# V1_sch.net
KiCad netlist of a schematic drawn in Altium Designer
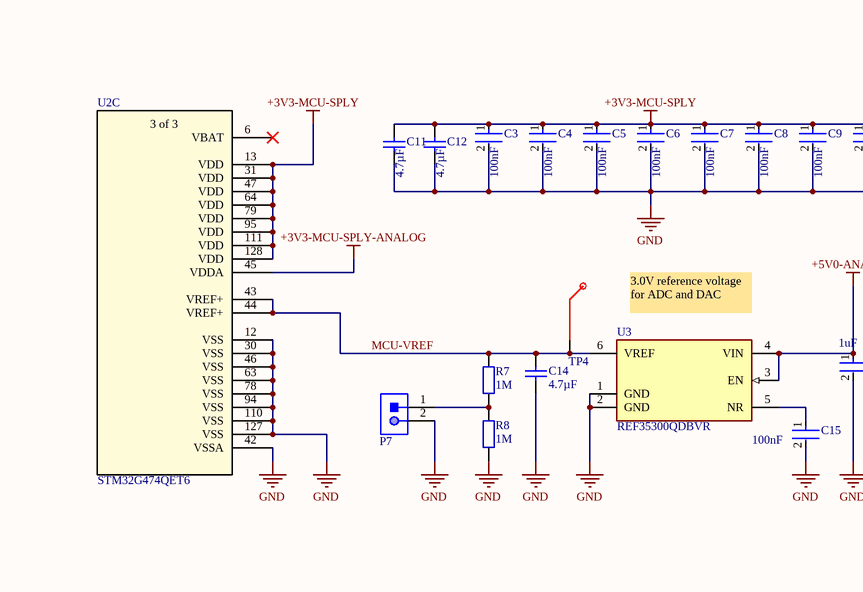
[diagram p0: V1_sch.SchDoc, top left]
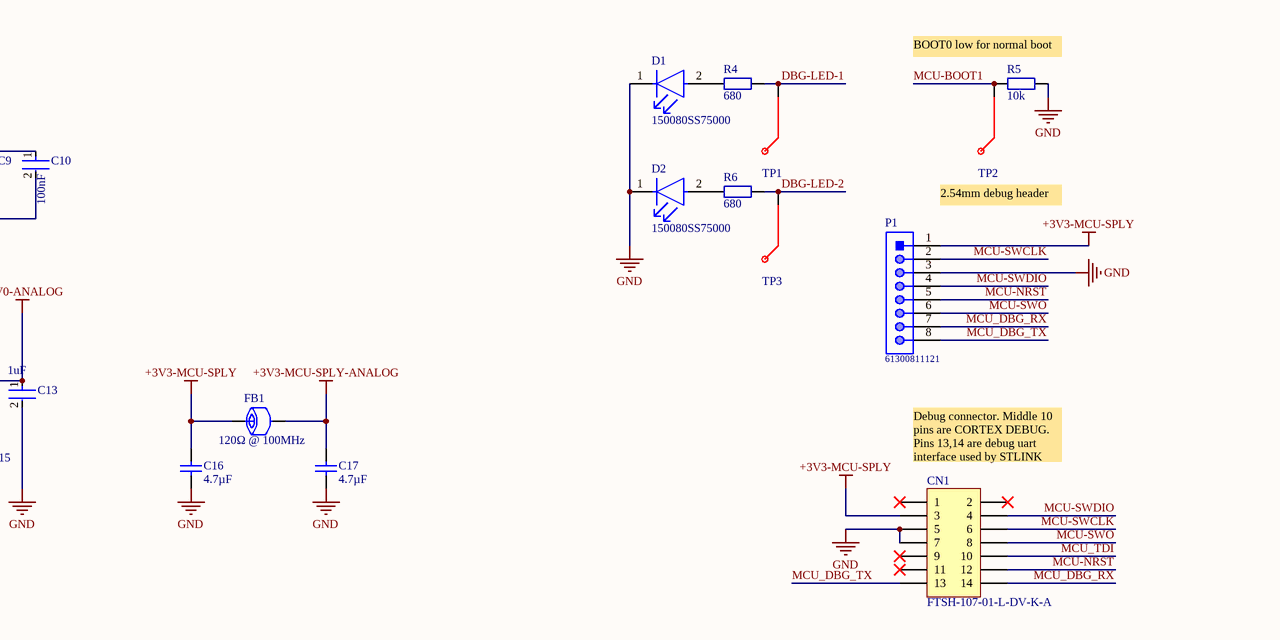
[diagram p1: V1_sch.SchDoc, top right]
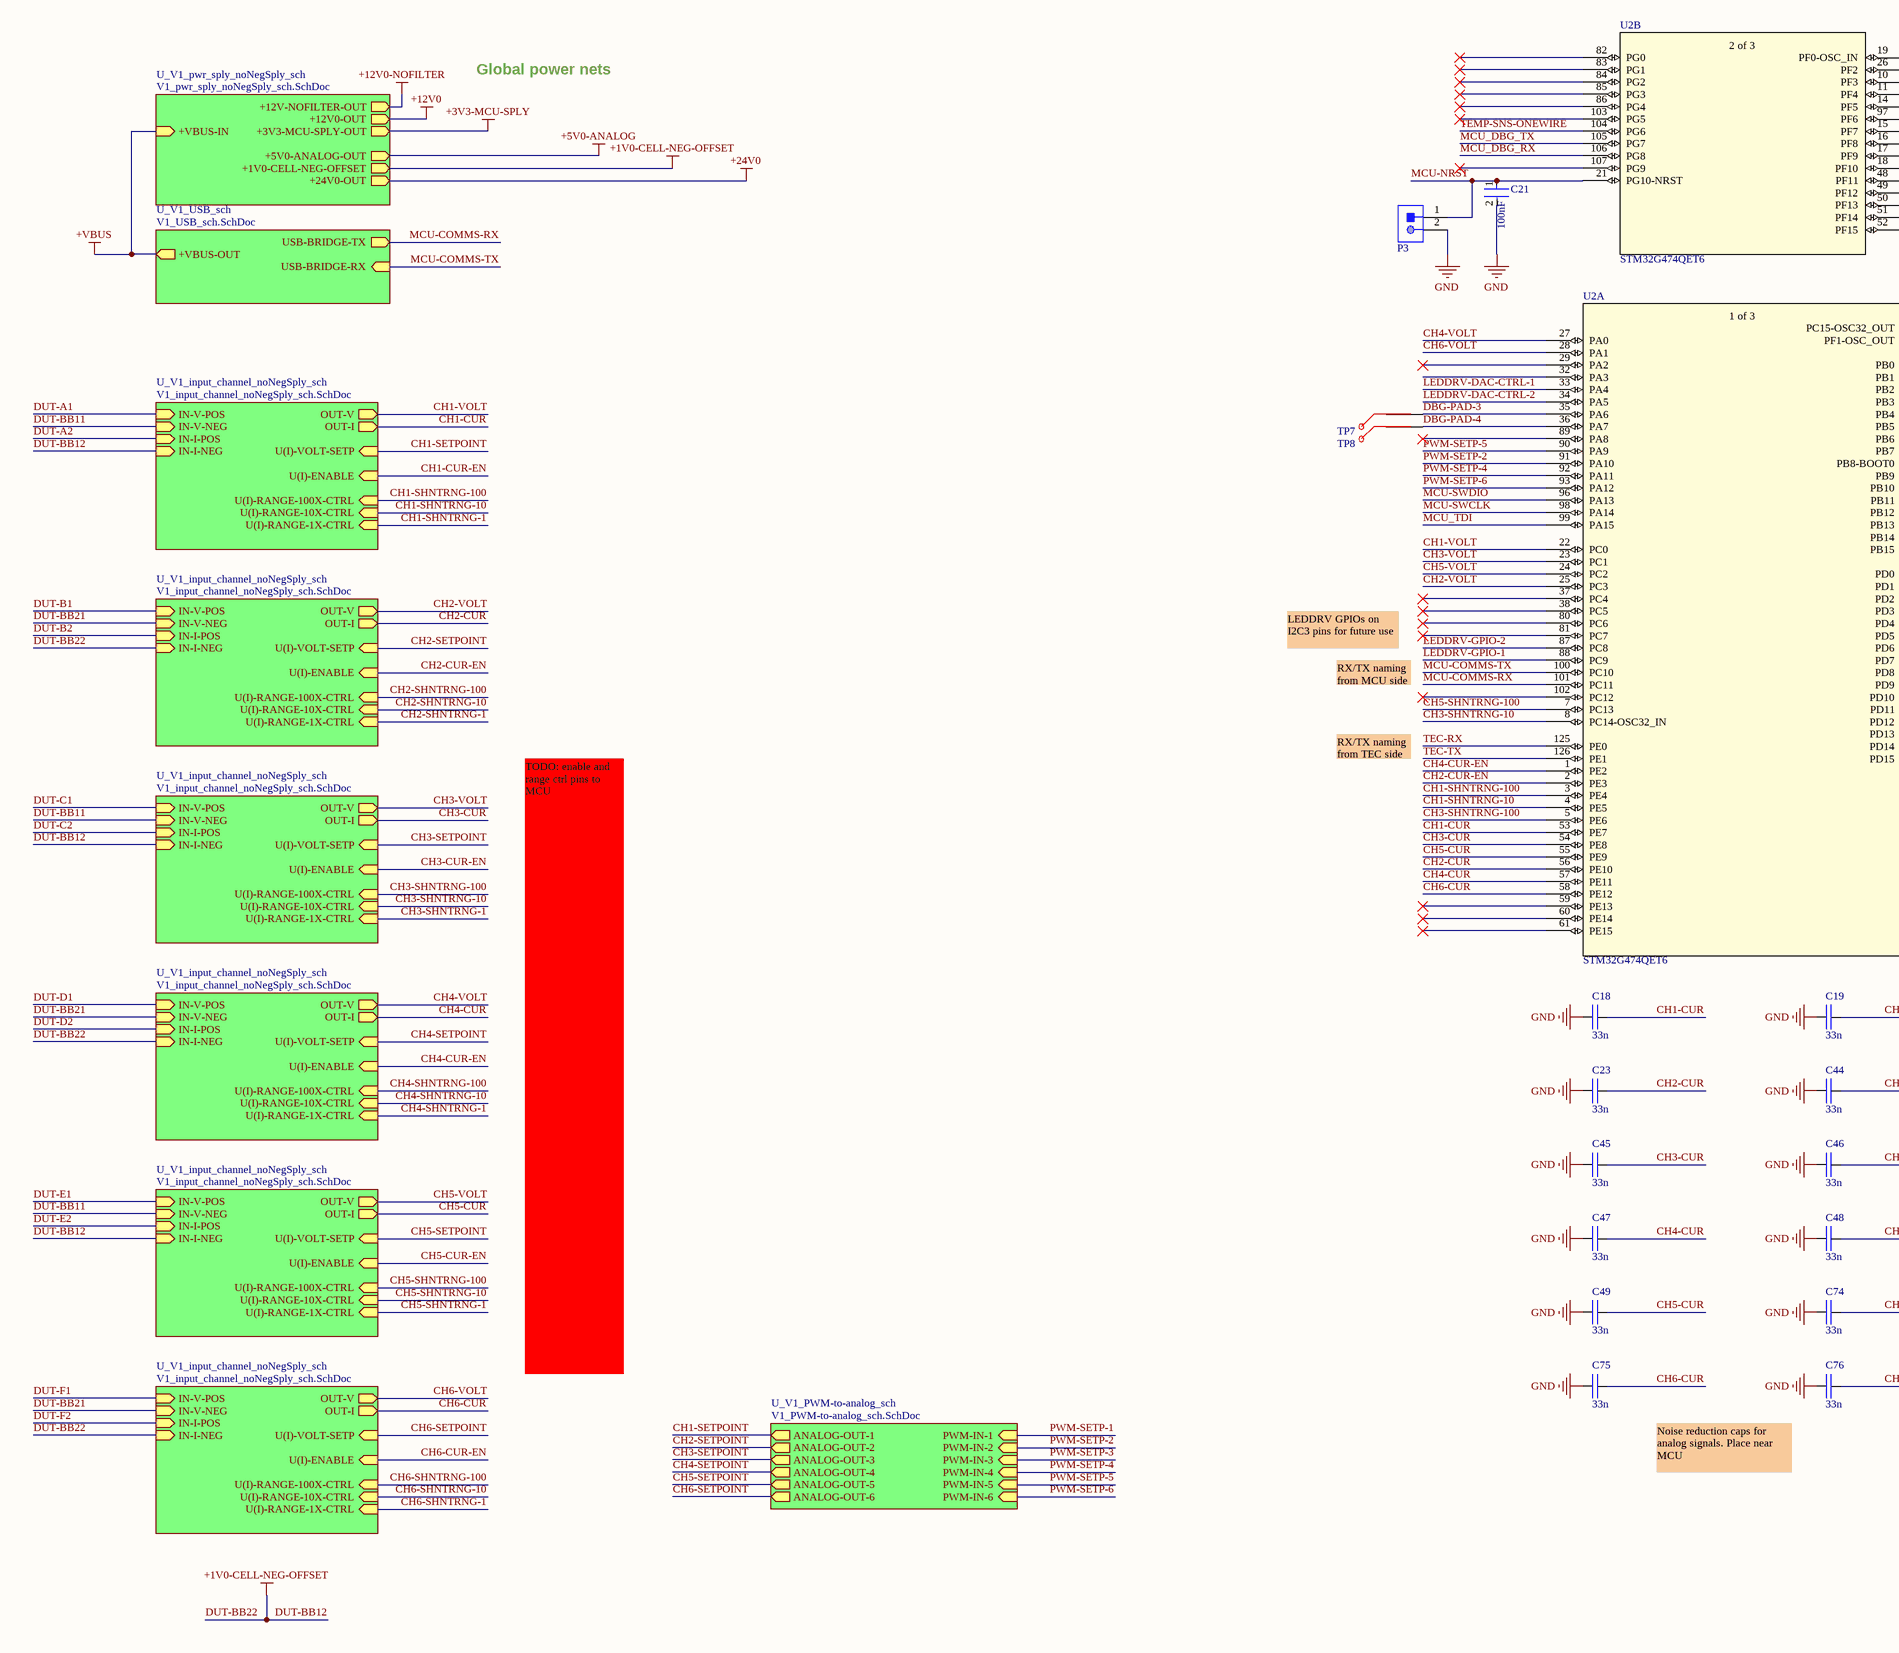
[diagram p2: V1_sch.SchDoc, bottom left]
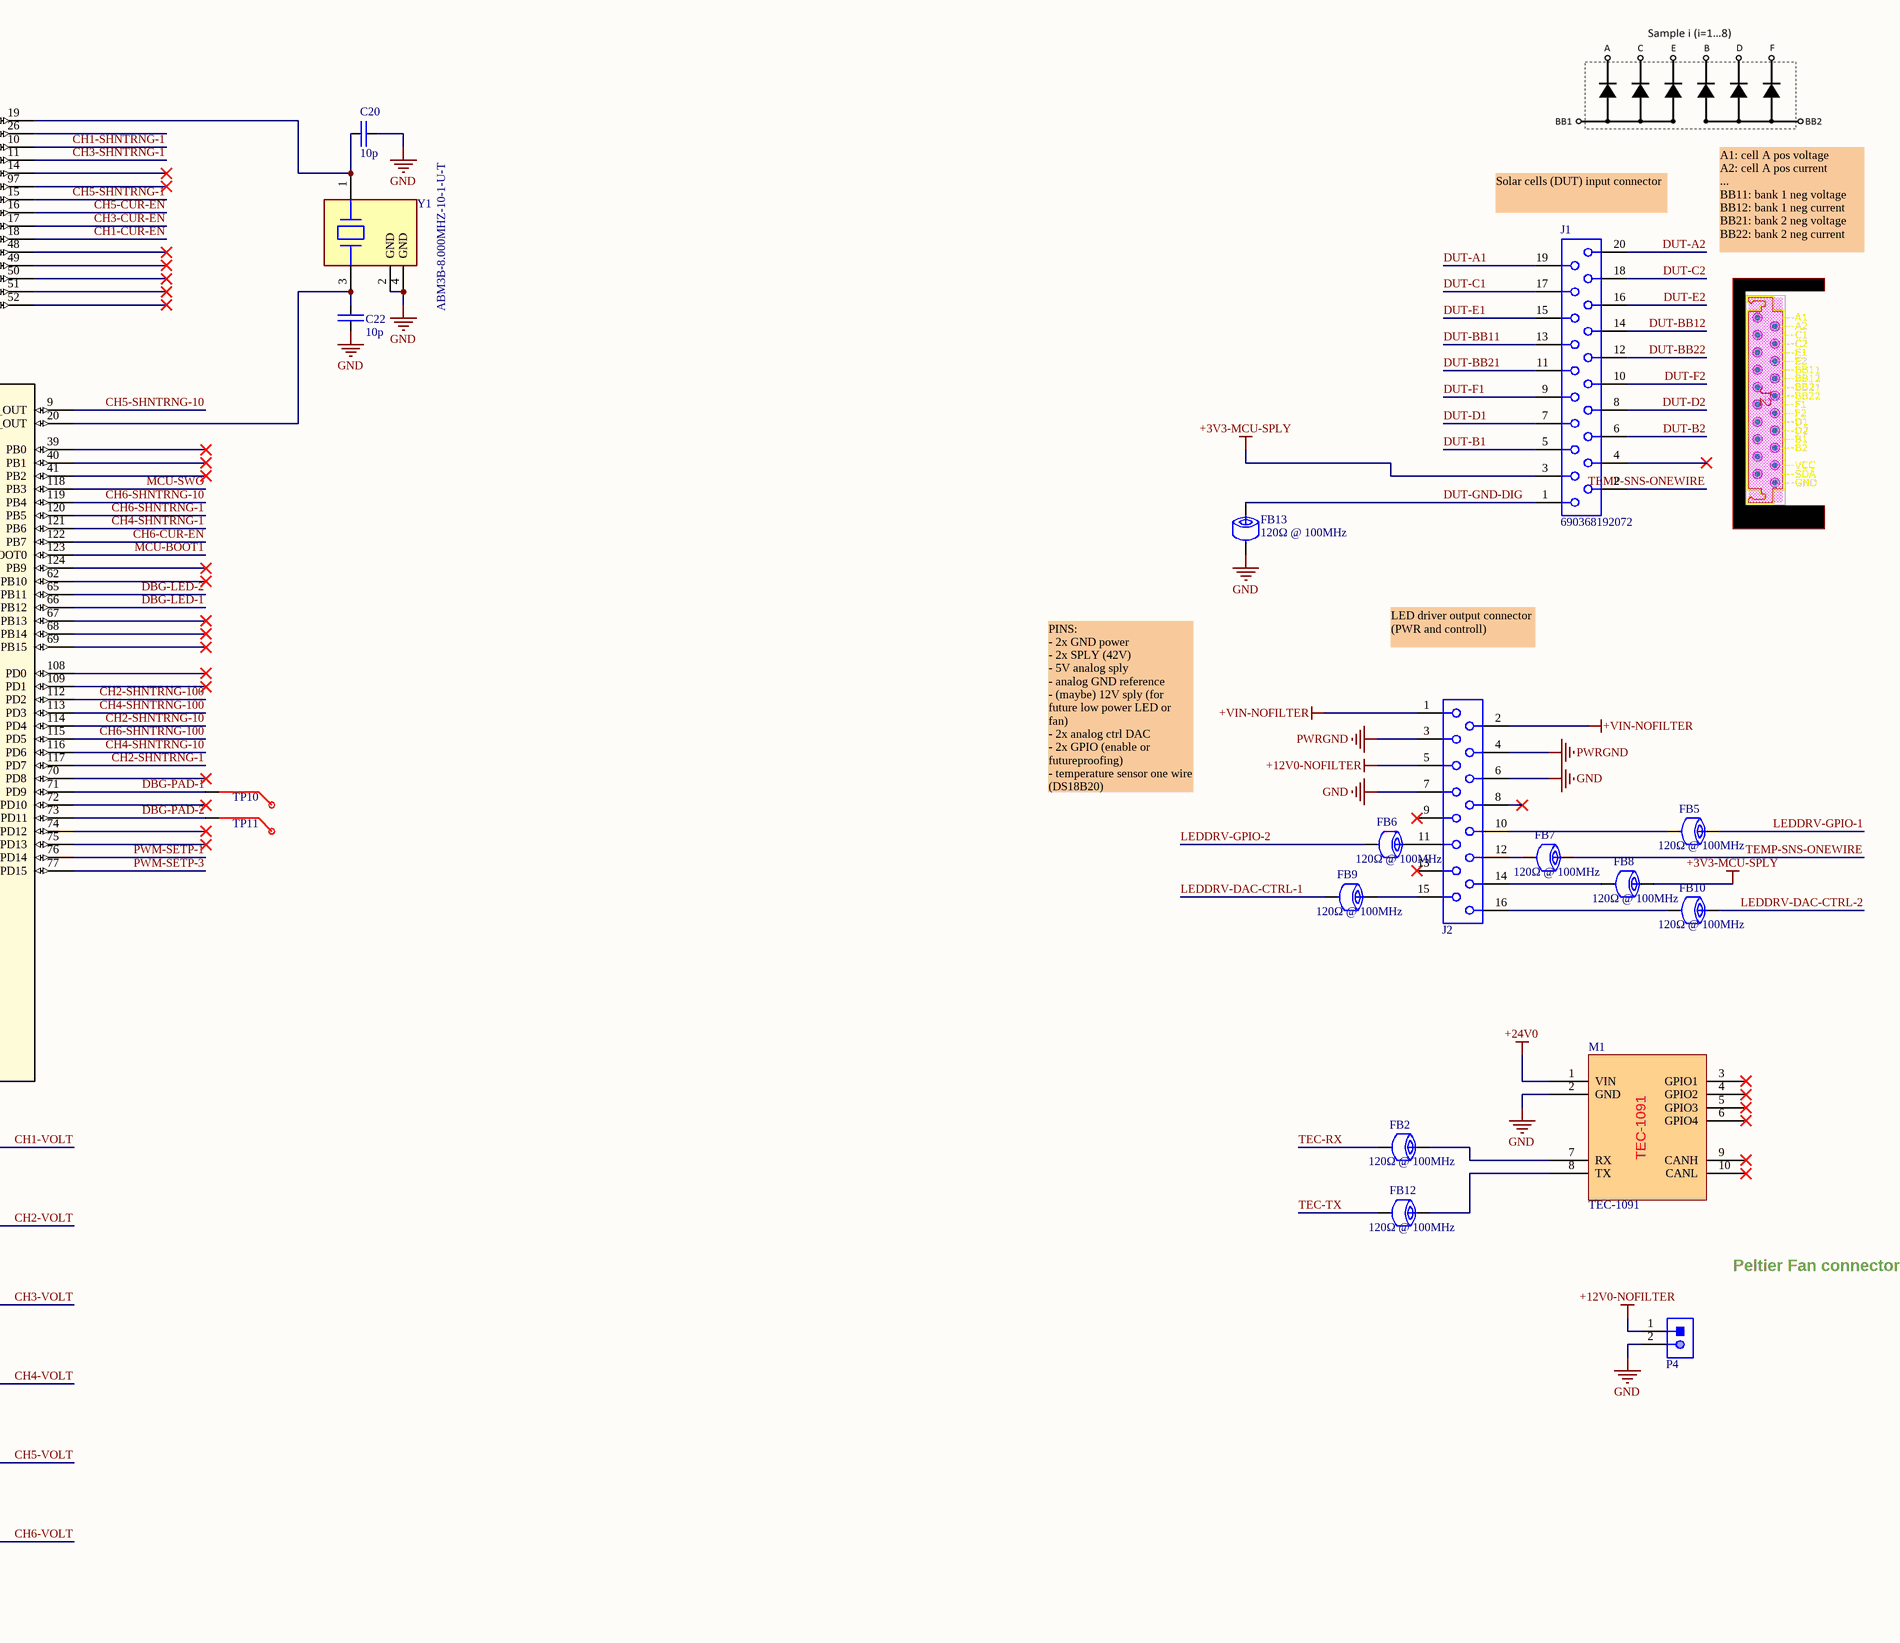
[diagram p3: V1_sch.SchDoc, bottom right]

(export (version "E")
  (design (tool "Eeschema 10.0.6"))
  (components
    (comp (ref "C3")
      (value "885012206095")
      (footprint "FP-885012206095-IPC_B")
      (description "CAP CER 0.1UF 50V X7R 0603")
      (fields (field (name "TOLERANCE") "10%") (field (name "CAPACITANCE") "100nF"))
      (libsource (lib "Altium Content Vault") (part "11868f565c42a9108669ba33697ecf6"))
    )
    (comp (ref "C4")
      (value "885012206095")
      (footprint "FP-885012206095-IPC_B")
      (description "CAP CER 0.1UF 50V X7R 0603")
      (fields (field (name "TOLERANCE") "10%") (field (name "CAPACITANCE") "100nF"))
      (libsource (lib "Altium Content Vault") (part "11868f565c42a9108669ba33697ecf6"))
    )
    (comp (ref "C5")
      (value "885012206095")
      (footprint "FP-885012206095-IPC_B")
      (description "CAP CER 0.1UF 50V X7R 0603")
      (fields (field (name "TOLERANCE") "10%") (field (name "CAPACITANCE") "100nF"))
      (libsource (lib "Altium Content Vault") (part "11868f565c42a9108669ba33697ecf6"))
    )
    (comp (ref "C6")
      (value "885012206095")
      (footprint "FP-885012206095-IPC_B")
      (description "CAP CER 0.1UF 50V X7R 0603")
      (fields (field (name "TOLERANCE") "10%") (field (name "CAPACITANCE") "100nF"))
      (libsource (lib "Altium Content Vault") (part "11868f565c42a9108669ba33697ecf6"))
    )
    (comp (ref "C7")
      (value "885012206095")
      (footprint "FP-885012206095-IPC_B")
      (description "CAP CER 0.1UF 50V X7R 0603")
      (fields (field (name "TOLERANCE") "10%") (field (name "CAPACITANCE") "100nF"))
      (libsource (lib "Altium Content Vault") (part "11868f565c42a9108669ba33697ecf6"))
    )
    (comp (ref "C8")
      (value "885012206095")
      (footprint "FP-885012206095-IPC_B")
      (description "CAP CER 0.1UF 50V X7R 0603")
      (fields (field (name "TOLERANCE") "10%") (field (name "CAPACITANCE") "100nF"))
      (libsource (lib "Altium Content Vault") (part "11868f565c42a9108669ba33697ecf6"))
    )
    (comp (ref "C9")
      (value "885012206095")
      (footprint "FP-885012206095-IPC_B")
      (description "CAP CER 0.1UF 50V X7R 0603")
      (fields (field (name "TOLERANCE") "10%") (field (name "CAPACITANCE") "100nF"))
      (libsource (lib "Altium Content Vault") (part "11868f565c42a9108669ba33697ecf6"))
    )
    (comp (ref "C10")
      (value "885012206095")
      (footprint "FP-885012206095-IPC_B")
      (description "CAP CER 0.1UF 50V X7R 0603")
      (fields (field (name "TOLERANCE") "10%") (field (name "CAPACITANCE") "100nF"))
      (libsource (lib "Altium Content Vault") (part "11868f565c42a9108669ba33697ecf6"))
    )
    (comp (ref "C11")
      (value "885012107018")
      (footprint "WCAP-CSGP_0805_L2W1.25H1.25")
      (description "WCAP-CSGP Multilayer Ceramic Chip Capacitor, General Purpose, size 0805, X5R, 4.7µF, 25VDC")
      (fields (field (name "MANUFACTURER") "Wurth Elektronik") (field (name "CAPACITANCE") "4.7µF"))
      (libsource (lib "Altium_WCAP-CSGP (rev22f)") (part "885012107018"))
    )
    (comp (ref "C12")
      (value "885012107018")
      (footprint "WCAP-CSGP_0805_L2W1.25H1.25")
      (description "WCAP-CSGP Multilayer Ceramic Chip Capacitor, General Purpose, size 0805, X5R, 4.7µF, 25VDC")
      (fields (field (name "MANUFACTURER") "Wurth Elektronik") (field (name "CAPACITANCE") "4.7µF"))
      (libsource (lib "Altium_WCAP-CSGP (rev22f)") (part "885012107018"))
    )
    (comp (ref "C13")
      (value "885012207078")
      (footprint "FP-885012207078-IPC_B")
      (description "CAP CER 1UF 25V X7R 0805")
      (fields (field (name "CAPACITANCE") "1uF") (field (name "TOLERANCE") "10%"))
      (libsource (lib "Altium Content Vault") (part "b4654b650e69147ec39a6b967a45e02"))
    )
    (comp (ref "C14")
      (value "885012107018")
      (footprint "WCAP-CSGP_0805_L2W1.25H1.25")
      (description "WCAP-CSGP Multilayer Ceramic Chip Capacitor, General Purpose, size 0805, X5R, 4.7µF, 25VDC")
      (fields (field (name "MANUFACTURER") "Wurth Elektronik") (field (name "CAPACITANCE") "4.7µF"))
      (libsource (lib "Altium_WCAP-CSGP (rev22f)") (part "885012107018"))
    )
    (comp (ref "C15")
      (value "885012206095")
      (footprint "FP-885012206095-IPC_B")
      (description "CAP CER 0.1UF 50V X7R 0603")
      (fields (field (name "TOLERANCE") "10%") (field (name "CAPACITANCE") "100nF"))
      (libsource (lib "Altium Content Vault") (part "11868f565c42a9108669ba33697ecf6"))
    )
    (comp (ref "C16")
      (value "885012107018")
      (footprint "WCAP-CSGP_0805_L2W1.25H1.25")
      (description "WCAP-CSGP Multilayer Ceramic Chip Capacitor, General Purpose, size 0805, X5R, 4.7µF, 25VDC")
      (fields (field (name "MANUFACTURER") "Wurth Elektronik") (field (name "CAPACITANCE") "4.7µF"))
      (libsource (lib "Altium_WCAP-CSGP (rev22f)") (part "885012107018"))
    )
    (comp (ref "C17")
      (value "885012107018")
      (footprint "WCAP-CSGP_0805_L2W1.25H1.25")
      (description "WCAP-CSGP Multilayer Ceramic Chip Capacitor, General Purpose, size 0805, X5R, 4.7µF, 25VDC")
      (fields (field (name "MANUFACTURER") "Wurth Elektronik") (field (name "CAPACITANCE") "4.7µF"))
      (libsource (lib "Altium_WCAP-CSGP (rev22f)") (part "885012107018"))
    )
    (comp (ref "C18")
      (value "33n")
      (footprint "Passives:FPR_0603_C_R0")
      (description "Capacitor - generic SMD")
      (fields (field (name "Comment") "PN_C0603_TBD"))
      (libsource (lib "Passives") (part "C"))
    )
    (comp (ref "C19")
      (value "33n")
      (footprint "Passives:FPR_0603_C_R0")
      (description "Capacitor - generic SMD")
      (fields (field (name "Comment") "PN_C0603_TBD"))
      (libsource (lib "Passives") (part "C"))
    )
    (comp (ref "C20")
      (value "10p")
      (footprint "Passives:FPR_0603_C_R0")
      (description "Capacitor - generic SMD")
      (fields (field (name "Comment") "PN_C0603_10p"))
      (libsource (lib "Passives") (part "C"))
    )
    (comp (ref "C21")
      (value "885012206095")
      (footprint "FP-885012206095-IPC_B")
      (description "CAP CER 0.1UF 50V X7R 0603")
      (fields (field (name "TOLERANCE") "10%") (field (name "CAPACITANCE") "100nF"))
      (libsource (lib "Altium Content Vault") (part "11868f565c42a9108669ba33697ecf6"))
    )
    (comp (ref "C22")
      (value "10p")
      (footprint "Passives:FPR_0603_C_R0")
      (description "Capacitor - generic SMD")
      (fields (field (name "Comment") "PN_C0603_10p"))
      (libsource (lib "Passives") (part "C"))
    )
    (comp (ref "C23")
      (value "33n")
      (footprint "Passives:FPR_0603_C_R0")
      (description "Capacitor - generic SMD")
      (fields (field (name "Comment") "PN_C0603_TBD"))
      (libsource (lib "Passives") (part "C"))
    )
    (comp (ref "C44")
      (value "33n")
      (footprint "Passives:FPR_0603_C_R0")
      (description "Capacitor - generic SMD")
      (fields (field (name "Comment") "PN_C0603_TBD"))
      (libsource (lib "Passives") (part "C"))
    )
    (comp (ref "C45")
      (value "33n")
      (footprint "Passives:FPR_0603_C_R0")
      (description "Capacitor - generic SMD")
      (fields (field (name "Comment") "PN_C0603_TBD"))
      (libsource (lib "Passives") (part "C"))
    )
    (comp (ref "C46")
      (value "33n")
      (footprint "Passives:FPR_0603_C_R0")
      (description "Capacitor - generic SMD")
      (fields (field (name "Comment") "PN_C0603_TBD"))
      (libsource (lib "Passives") (part "C"))
    )
    (comp (ref "C47")
      (value "33n")
      (footprint "Passives:FPR_0603_C_R0")
      (description "Capacitor - generic SMD")
      (fields (field (name "Comment") "PN_C0603_TBD"))
      (libsource (lib "Passives") (part "C"))
    )
    (comp (ref "C48")
      (value "33n")
      (footprint "Passives:FPR_0603_C_R0")
      (description "Capacitor - generic SMD")
      (fields (field (name "Comment") "PN_C0603_TBD"))
      (libsource (lib "Passives") (part "C"))
    )
    (comp (ref "C49")
      (value "33n")
      (footprint "Passives:FPR_0603_C_R0")
      (description "Capacitor - generic SMD")
      (fields (field (name "Comment") "PN_C0603_TBD"))
      (libsource (lib "Passives") (part "C"))
    )
    (comp (ref "C74")
      (value "33n")
      (footprint "Passives:FPR_0603_C_R0")
      (description "Capacitor - generic SMD")
      (fields (field (name "Comment") "PN_C0603_TBD"))
      (libsource (lib "Passives") (part "C"))
    )
    (comp (ref "C75")
      (value "33n")
      (footprint "Passives:FPR_0603_C_R0")
      (description "Capacitor - generic SMD")
      (fields (field (name "Comment") "PN_C0603_TBD"))
      (libsource (lib "Passives") (part "C"))
    )
    (comp (ref "C76")
      (value "33n")
      (footprint "Passives:FPR_0603_C_R0")
      (description "Capacitor - generic SMD")
      (fields (field (name "Comment") "PN_C0603_TBD"))
      (libsource (lib "Passives") (part "C"))
    )
    (comp (ref "CN1")
      (value "FTSH-107-01-L-DV-K-A")
      (footprint "CON_STDC14_Receiver_MEDIUM_WITH_MIPI10_3D")
      (libsource (lib "IMS_library") (part "FTSH-107-01-L-DV-K-A"))
    )
    (comp (ref "D1")
      (value "150080SS75000")
      (footprint "FP-150080SS75000-MFG")
      (description "LED RED CLEAR 0805 SMD")
      (libsource (lib "Altium Content Vault") (part "8706943c75ba83719d021d2fdc84c58"))
    )
    (comp (ref "D2")
      (value "150080SS75000")
      (footprint "FP-150080SS75000-MFG")
      (description "LED RED CLEAR 0805 SMD")
      (libsource (lib "Altium Content Vault") (part "8706943c75ba83719d021d2fdc84c58"))
    )
    (comp (ref "FB1")
      (value "120Ω @ 100MHz")
      (footprint "SMD_0805")
      (description "Ferrite Bead, 0805 [2012 Metric], 120 ohm, 800 mA, BLM21A Series, 0.15 ohm, ± 25%")
      (fields (field (name "MANUFACTURER") "Murata"))
      (libsource (lib "DAQ_REV_B") (part "BLM21AG121SN1D"))
    )
    (comp (ref "FB2")
      (value "120Ω @ 100MHz")
      (footprint "SMD_0805")
      (description "Ferrite Bead, 0805 [2012 Metric], 120 ohm, 800 mA, BLM21A Series, 0.15 ohm, ± 25%")
      (fields (field (name "MANUFACTURER") "Murata"))
      (libsource (lib "DAQ_REV_B") (part "BLM21AG121SN1D"))
    )
    (comp (ref "FB5")
      (value "120Ω @ 100MHz")
      (footprint "SMD_0805")
      (description "Ferrite Bead, 0805 [2012 Metric], 120 ohm, 800 mA, BLM21A Series, 0.15 ohm, ± 25%")
      (fields (field (name "MANUFACTURER") "Murata"))
      (libsource (lib "DAQ_REV_B") (part "BLM21AG121SN1D"))
    )
    (comp (ref "FB6")
      (value "120Ω @ 100MHz")
      (footprint "SMD_0805")
      (description "Ferrite Bead, 0805 [2012 Metric], 120 ohm, 800 mA, BLM21A Series, 0.15 ohm, ± 25%")
      (fields (field (name "MANUFACTURER") "Murata"))
      (libsource (lib "DAQ_REV_B") (part "BLM21AG121SN1D"))
    )
    (comp (ref "FB7")
      (value "120Ω @ 100MHz")
      (footprint "SMD_0805")
      (description "Ferrite Bead, 0805 [2012 Metric], 120 ohm, 800 mA, BLM21A Series, 0.15 ohm, ± 25%")
      (fields (field (name "MANUFACTURER") "Murata"))
      (libsource (lib "DAQ_REV_B") (part "BLM21AG121SN1D"))
    )
    (comp (ref "FB8")
      (value "120Ω @ 100MHz")
      (footprint "SMD_0805")
      (description "Ferrite Bead, 0805 [2012 Metric], 120 ohm, 800 mA, BLM21A Series, 0.15 ohm, ± 25%")
      (fields (field (name "MANUFACTURER") "Murata"))
      (libsource (lib "DAQ_REV_B") (part "BLM21AG121SN1D"))
    )
    (comp (ref "FB9")
      (value "120Ω @ 100MHz")
      (footprint "SMD_0805")
      (description "Ferrite Bead, 0805 [2012 Metric], 120 ohm, 800 mA, BLM21A Series, 0.15 ohm, ± 25%")
      (fields (field (name "MANUFACTURER") "Murata"))
      (libsource (lib "DAQ_REV_B") (part "BLM21AG121SN1D"))
    )
    (comp (ref "FB10")
      (value "120Ω @ 100MHz")
      (footprint "SMD_0805")
      (description "Ferrite Bead, 0805 [2012 Metric], 120 ohm, 800 mA, BLM21A Series, 0.15 ohm, ± 25%")
      (fields (field (name "MANUFACTURER") "Murata"))
      (libsource (lib "DAQ_REV_B") (part "BLM21AG121SN1D"))
    )
    (comp (ref "FB12")
      (value "120Ω @ 100MHz")
      (footprint "SMD_0805")
      (description "Ferrite Bead, 0805 [2012 Metric], 120 ohm, 800 mA, BLM21A Series, 0.15 ohm, ± 25%")
      (fields (field (name "MANUFACTURER") "Murata"))
      (libsource (lib "DAQ_REV_B") (part "BLM21AG121SN1D"))
    )
    (comp (ref "FB13")
      (value "120Ω @ 100MHz")
      (footprint "SMD_0805")
      (description "Ferrite Bead, 0805 [2012 Metric], 120 ohm, 800 mA, BLM21A Series, 0.15 ohm, ± 25%")
      (fields (field (name "MANUFACTURER") "Murata"))
      (libsource (lib "DAQ_REV_B") (part "BLM21AG121SN1D"))
    )
    (comp (ref "J1")
      (value "690368192072")
      (footprint "690368192072")
      (description "WR-MM Mini Module Connector, Female, THT, with Latch & Polarization, Angled, pitch 2.54mm, 20p")
      (fields (field (name "MANUFACTURER") "Wurth Elektronik"))
      (libsource (lib "Altium_WR-MM (rev22a)") (part "690368192072"))
    )
    (comp (ref "J2")
      (value "690368191672")
      (footprint "690368191672")
      (description "WR-MM Mini Module Connector, Female, THT, with Latch & Polarization, Angled, pitch 2.54mm, 16p")
      (fields (field (name "MANUFACTURER") "Wurth Elektronik"))
      (libsource (lib "Altium_WR-MM (rev22a)") (part "690368191672"))
    )
    (comp (ref "M1")
      (value "TEC-1091")
      (footprint "tec1091-pins")
      (description "Peltier control module")
      (libsource (lib "TEC1091") (part "TEC-1091"))
    )
    (comp (ref "P1")
      (value "61300811121")
      (footprint "61300811121")
      (description "THT Vertical Pin Header WR-PHD, Pitch 2.54 mm, Single Row, 8 pins")
      (fields (field (name "MANUFACTURER") "Wurth Elektronik") (field (name "PUBLISHER") "WurthElektronik"))
      (libsource (lib "Components - 22.06.23 - 11.05") (part "CMP-1502-01076-1"))
    )
    (comp (ref "P3")
      (value "61300211121")
      (footprint "61300211121")
      (description "THT Vertical Pin Header WR-PHD, Pitch 2.54 mm, Single Row, 2 pins")
      (fields (field (name "MANUFACTURER") "Wurth Elektronik") (field (name "PUBLISHER") "WurthElektronik"))
      (libsource (lib "Altium Content Vault") (part "WE-CN-1P-M-R2"))
    )
    (comp (ref "P4")
      (value "61300211121")
      (footprint "61300211121")
      (description "THT Vertical Pin Header WR-PHD, Pitch 2.54 mm, Single Row, 2 pins")
      (fields (field (name "MANUFACTURER") "Wurth Elektronik") (field (name "PUBLISHER") "WurthElektronik"))
      (libsource (lib "") (part "WE-CN-1P-M-R2_1"))
    )
    (comp (ref "P7")
      (value "61300211121")
      (footprint "61300211121")
      (description "THT Vertical Pin Header WR-PHD, Pitch 2.54 mm, Single Row, 2 pins")
      (fields (field (name "MANUFACTURER") "Wurth Elektronik") (field (name "PUBLISHER") "WurthElektronik"))
      (libsource (lib "Altium Content Vault") (part "WE-CN-1P-M-R2"))
    )
    (comp (ref "R4")
      (value "680")
      (footprint "Passives:FPR_0603_R_R0")
      (description "Resistor - generic SMD")
      (fields (field (name "Comment") "PN_R0603_680R"))
      (libsource (lib "Passives") (part "R"))
    )
    (comp (ref "R5")
      (value "10k")
      (footprint "Passives:FPR_0603_R_R0")
      (description "Resistor - generic SMD")
      (fields (field (name "Comment") "PN_R0603_10k"))
      (libsource (lib "Passives") (part "R"))
    )
    (comp (ref "R6")
      (value "680")
      (footprint "Passives:FPR_0603_R_R0")
      (description "Resistor - generic SMD")
      (fields (field (name "Comment") "PN_R0603_680R"))
      (libsource (lib "Passives") (part "R"))
    )
    (comp (ref "R7")
      (value "1M")
      (footprint "Passives:FPR_0603_R_R0")
      (description "Resistor - generic SMD")
      (fields (field (name "Comment") "PN_R0603_1M"))
      (libsource (lib "Passives") (part "R"))
    )
    (comp (ref "R8")
      (value "1M")
      (footprint "Passives:FPR_0603_R_R0")
      (description "Resistor - generic SMD")
      (fields (field (name "Comment") "PN_R0603_1M"))
      (libsource (lib "Passives") (part "R"))
    )
    (comp (ref "TP1")
      (value "Test Point")
      (footprint "Test Point 1.5mm SMD")
      (libsource (lib "planinsekLib_sch") (part "Test Point"))
    )
    (comp (ref "TP2")
      (value "Test Point")
      (footprint "Test Point 1.5mm SMD")
      (libsource (lib "planinsekLib_sch") (part "Test Point"))
    )
    (comp (ref "TP3")
      (value "Test Point")
      (footprint "Test Point 1.5mm SMD")
      (libsource (lib "planinsekLib_sch") (part "Test Point"))
    )
    (comp (ref "TP4")
      (value "Test Point")
      (footprint "Test Point 1.5mm SMD")
      (libsource (lib "planinsekLib_sch") (part "Test Point"))
    )
    (comp (ref "TP7")
      (value "Test Point")
      (footprint "Test Point 1.5mm SMD")
      (libsource (lib "planinsekLib_sch") (part "Test Point"))
    )
    (comp (ref "TP8")
      (value "Test Point")
      (footprint "Test Point 1.5mm SMD")
      (libsource (lib "planinsekLib_sch") (part "Test Point"))
    )
    (comp (ref "TP10")
      (value "Test Point")
      (footprint "Test Point 1.5mm SMD")
      (libsource (lib "planinsekLib_sch") (part "Test Point"))
    )
    (comp (ref "TP11")
      (value "Test Point")
      (footprint "Test Point 1.5mm SMD")
      (libsource (lib "planinsekLib_sch") (part "Test Point"))
    )
    (comp (ref "U2")
      (value "STM32G474QET6")
      (footprint "LPQFP-128")
      (description "No Description Available")
      (libsource (lib "") (part "STM32G474QET6_1"))
    )
    (comp (ref "U3")
      (value "REF35300QDBVR")
      (footprint "FP-DBV0006A-MFG")
      (description "650-NA QUIESCENT CURRENT, 12-PPM, 3V out")
      (libsource (lib "Altium Content Vault") (part "73067d3f248247d8aed0d86424b3493"))
    )
    (comp (ref "Y1")
      (value "ABM3B-8.000MHZ-10-1-U-T")
      (footprint "FP-ABM3B-MFG")
      (description "Crystal 8MHz ±10ppm 10pF SMD-4 5mm x 3.2mm")
      (libsource (lib "Altium Content Vault") (part "48e526d86b7f2615d98721063c72f49"))
    )
  )
  (nets
    (net (code "1") (name "+1V0-CELL-NEG-OFFSET") (class "Default")
      (node (ref "J1") (pin "12") (pinfunction "12_12") (pintype "passive"))
      (node (ref "J1") (pin "14") (pinfunction "14_14") (pintype "passive"))
    )
    (net (code "2") (name "+3V3-MCU-SPLY") (class "Default")
      (node (ref "C10") (pin "1") (pinfunction "1_1") (pintype "passive"))
      (node (ref "C11") (pin "2") (pinfunction "2_2") (pintype "passive"))
      (node (ref "C12") (pin "2") (pinfunction "2_2") (pintype "passive"))
      (node (ref "C16") (pin "2") (pinfunction "2_2") (pintype "passive"))
      (node (ref "C3") (pin "1") (pinfunction "1_1") (pintype "passive"))
      (node (ref "C4") (pin "1") (pinfunction "1_1") (pintype "passive"))
      (node (ref "C5") (pin "1") (pinfunction "1_1") (pintype "passive"))
      (node (ref "C6") (pin "1") (pinfunction "1_1") (pintype "passive"))
      (node (ref "C7") (pin "1") (pinfunction "1_1") (pintype "passive"))
      (node (ref "C8") (pin "1") (pinfunction "1_1") (pintype "passive"))
      (node (ref "C9") (pin "1") (pinfunction "1_1") (pintype "passive"))
      (node (ref "CN1") (pin "3") (pinfunction "3_3") (pintype "passive"))
      (node (ref "FB1") (pin "1") (pintype "passive"))
      (node (ref "FB8") (pin "1") (pintype "passive"))
      (node (ref "J1") (pin "3") (pinfunction "3_3") (pintype "passive"))
      (node (ref "P1") (pin "1") (pinfunction "1_1") (pintype "passive"))
      (node (ref "U2") (pin "111") (pinfunction "VDD_111") (pintype "power_in"))
      (node (ref "U2") (pin "128") (pinfunction "VDD_128") (pintype "power_in"))
      (node (ref "U2") (pin "13") (pinfunction "VDD_13") (pintype "power_in"))
      (node (ref "U2") (pin "31") (pinfunction "VDD_31") (pintype "power_in"))
      (node (ref "U2") (pin "47") (pinfunction "VDD_47") (pintype "power_in"))
      (node (ref "U2") (pin "64") (pinfunction "VDD_64") (pintype "power_in"))
      (node (ref "U2") (pin "79") (pinfunction "VDD_79") (pintype "power_in"))
      (node (ref "U2") (pin "95") (pinfunction "VDD_95") (pintype "power_in"))
    )
    (net (code "3") (name "+3V3-MCU-SPLY-ANALOG") (class "Default")
      (node (ref "C17") (pin "2") (pinfunction "2_2") (pintype "passive"))
      (node (ref "FB1") (pin "2") (pintype "passive"))
      (node (ref "U2") (pin "45") (pinfunction "VDDA_45") (pintype "power_in"))
    )
    (net (code "4") (name "+5V0-ANALOG") (class "Default")
      (node (ref "C13") (pin "1") (pinfunction "1_1") (pintype "passive"))
      (node (ref "U3") (pin "3") (pinfunction "EN_3") (pintype "input"))
      (node (ref "U3") (pin "4") (pinfunction "VIN_4") (pintype "power_in"))
    )
    (net (code "6") (name "+12V0-NOFILTER") (class "Default")
      (node (ref "J2") (pin "5") (pinfunction "5_5") (pintype "passive"))
      (node (ref "P4") (pin "1") (pinfunction "1_1") (pintype "passive"))
    )
    (net (code "7") (name "+24V0") (class "Default")
      (node (ref "M1") (pin "1") (pinfunction "VIN_1") (pintype "passive"))
    )
    (net (code "9") (name "+VIN-NOFILTER") (class "Default")
      (node (ref "J2") (pin "1") (pinfunction "1_1") (pintype "passive"))
      (node (ref "J2") (pin "2") (pinfunction "2_2") (pintype "passive"))
    )
    (net (code "10") (name "/CH1-CUR") (class "Default")
      (node (ref "C18") (pin "1") (pinfunction "1_1") (pintype "passive"))
      (node (ref "U2") (pin "53") (pinfunction "PE7_53") (pintype "bidirectional"))
    )
    (net (code "11") (name "/CH1-CUR-EN") (class "Default")
      (node (ref "U2") (pin "18") (pinfunction "PF10_18") (pintype "bidirectional"))
    )
    (net (code "13") (name "/CH1-SHNTRNG-1") (class "Default")
      (node (ref "U2") (pin "10") (pinfunction "PF3_10") (pintype "bidirectional"))
    )
    (net (code "14") (name "/CH1-SHNTRNG-10") (class "Default")
      (node (ref "U2") (pin "4") (pinfunction "PE5_4") (pintype "bidirectional"))
    )
    (net (code "15") (name "/CH1-SHNTRNG-100") (class "Default")
      (node (ref "U2") (pin "3") (pinfunction "PE4_3") (pintype "bidirectional"))
    )
    (net (code "16") (name "/CH1-VOLT") (class "Default")
      (node (ref "C19") (pin "1") (pinfunction "1_1") (pintype "passive"))
      (node (ref "U2") (pin "22") (pinfunction "PC0_22") (pintype "bidirectional"))
    )
    (net (code "17") (name "/CH2-CUR") (class "Default")
      (node (ref "C23") (pin "1") (pinfunction "1_1") (pintype "passive"))
      (node (ref "U2") (pin "56") (pinfunction "PE10_56") (pintype "bidirectional"))
    )
    (net (code "18") (name "/CH2-CUR-EN") (class "Default")
      (node (ref "U2") (pin "2") (pinfunction "PE3_2") (pintype "bidirectional"))
    )
    (net (code "20") (name "/CH2-SHNTRNG-1") (class "Default")
      (node (ref "U2") (pin "117") (pinfunction "PD7_117") (pintype "bidirectional"))
    )
    (net (code "21") (name "/CH2-SHNTRNG-10") (class "Default")
      (node (ref "U2") (pin "114") (pinfunction "PD4_114") (pintype "bidirectional"))
    )
    (net (code "22") (name "/CH2-SHNTRNG-100") (class "Default")
      (node (ref "U2") (pin "112") (pinfunction "PD2_112") (pintype "bidirectional"))
    )
    (net (code "23") (name "/CH2-VOLT") (class "Default")
      (node (ref "C44") (pin "1") (pinfunction "1_1") (pintype "passive"))
      (node (ref "U2") (pin "25") (pinfunction "PC3_25") (pintype "bidirectional"))
    )
    (net (code "24") (name "/CH3-CUR") (class "Default")
      (node (ref "C45") (pin "1") (pinfunction "1_1") (pintype "passive"))
      (node (ref "U2") (pin "54") (pinfunction "PE8_54") (pintype "bidirectional"))
    )
    (net (code "25") (name "/CH3-CUR-EN") (class "Default")
      (node (ref "U2") (pin "17") (pinfunction "PF9_17") (pintype "bidirectional"))
    )
    (net (code "27") (name "/CH3-SHNTRNG-1") (class "Default")
      (node (ref "U2") (pin "11") (pinfunction "PF4_11") (pintype "bidirectional"))
    )
    (net (code "28") (name "/CH3-SHNTRNG-10") (class "Default")
      (node (ref "U2") (pin "8") (pinfunction "PC14-OSC32_IN_8") (pintype "bidirectional"))
    )
    (net (code "29") (name "/CH3-SHNTRNG-100") (class "Default")
      (node (ref "U2") (pin "5") (pinfunction "PE6_5") (pintype "bidirectional"))
    )
    (net (code "30") (name "/CH3-VOLT") (class "Default")
      (node (ref "C46") (pin "1") (pinfunction "1_1") (pintype "passive"))
      (node (ref "U2") (pin "23") (pinfunction "PC1_23") (pintype "bidirectional"))
    )
    (net (code "31") (name "/CH4-CUR") (class "Default")
      (node (ref "C47") (pin "1") (pinfunction "1_1") (pintype "passive"))
      (node (ref "U2") (pin "57") (pinfunction "PE11_57") (pintype "bidirectional"))
    )
    (net (code "32") (name "/CH4-CUR-EN") (class "Default")
      (node (ref "U2") (pin "1") (pinfunction "PE2_1") (pintype "bidirectional"))
    )
    (net (code "34") (name "/CH4-SHNTRNG-1") (class "Default")
      (node (ref "U2") (pin "121") (pinfunction "PB6_121") (pintype "bidirectional"))
    )
    (net (code "35") (name "/CH4-SHNTRNG-10") (class "Default")
      (node (ref "U2") (pin "116") (pinfunction "PD6_116") (pintype "bidirectional"))
    )
    (net (code "36") (name "/CH4-SHNTRNG-100") (class "Default")
      (node (ref "U2") (pin "113") (pinfunction "PD3_113") (pintype "bidirectional"))
    )
    (net (code "37") (name "/CH4-VOLT") (class "Default")
      (node (ref "C48") (pin "1") (pinfunction "1_1") (pintype "passive"))
      (node (ref "U2") (pin "27") (pinfunction "PA0_27") (pintype "bidirectional"))
    )
    (net (code "38") (name "/CH5-CUR") (class "Default")
      (node (ref "C49") (pin "1") (pinfunction "1_1") (pintype "passive"))
      (node (ref "U2") (pin "55") (pinfunction "PE9_55") (pintype "bidirectional"))
    )
    (net (code "39") (name "/CH5-CUR-EN") (class "Default")
      (node (ref "U2") (pin "16") (pinfunction "PF8_16") (pintype "bidirectional"))
    )
    (net (code "41") (name "/CH5-SHNTRNG-1") (class "Default")
      (node (ref "U2") (pin "15") (pinfunction "PF7_15") (pintype "bidirectional"))
    )
    (net (code "42") (name "/CH5-SHNTRNG-10") (class "Default")
      (node (ref "U2") (pin "9") (pinfunction "PC15-OSC32_OUT_9") (pintype "bidirectional"))
    )
    (net (code "43") (name "/CH5-SHNTRNG-100") (class "Default")
      (node (ref "U2") (pin "7") (pinfunction "PC13_7") (pintype "bidirectional"))
    )
    (net (code "44") (name "/CH5-VOLT") (class "Default")
      (node (ref "C74") (pin "1") (pinfunction "1_1") (pintype "passive"))
      (node (ref "U2") (pin "24") (pinfunction "PC2_24") (pintype "bidirectional"))
    )
    (net (code "45") (name "/CH6-CUR") (class "Default")
      (node (ref "C75") (pin "1") (pinfunction "1_1") (pintype "passive"))
      (node (ref "U2") (pin "58") (pinfunction "PE12_58") (pintype "bidirectional"))
    )
    (net (code "46") (name "/CH6-CUR-EN") (class "Default")
      (node (ref "U2") (pin "122") (pinfunction "PB7_122") (pintype "bidirectional"))
    )
    (net (code "48") (name "/CH6-SHNTRNG-1") (class "Default")
      (node (ref "U2") (pin "120") (pinfunction "PB5_120") (pintype "bidirectional"))
    )
    (net (code "49") (name "/CH6-SHNTRNG-10") (class "Default")
      (node (ref "U2") (pin "119") (pinfunction "PB4_119") (pintype "bidirectional"))
    )
    (net (code "50") (name "/CH6-SHNTRNG-100") (class "Default")
      (node (ref "U2") (pin "115") (pinfunction "PD5_115") (pintype "bidirectional"))
    )
    (net (code "51") (name "/CH6-VOLT") (class "Default")
      (node (ref "C76") (pin "1") (pinfunction "1_1") (pintype "passive"))
      (node (ref "U2") (pin "28") (pinfunction "PA1_28") (pintype "bidirectional"))
    )
    (net (code "52") (name "/DBG-LED-1") (class "Default")
      (node (ref "R4") (pin "1") (pinfunction "1_1") (pintype "passive"))
      (node (ref "TP1") (pin "1") (pintype "passive"))
      (node (ref "U2") (pin "66") (pinfunction "PB12_66") (pintype "bidirectional"))
    )
    (net (code "53") (name "/DBG-LED-2") (class "Default")
      (node (ref "R6") (pin "1") (pinfunction "1_1") (pintype "passive"))
      (node (ref "TP3") (pin "1") (pintype "passive"))
      (node (ref "U2") (pin "65") (pinfunction "PB11_65") (pintype "bidirectional"))
    )
    (net (code "54") (name "/DBG-PAD-1") (class "Default")
      (node (ref "TP10") (pin "1") (pintype "passive"))
      (node (ref "U2") (pin "71") (pinfunction "PD9_71") (pintype "bidirectional"))
    )
    (net (code "55") (name "/DBG-PAD-2") (class "Default")
      (node (ref "TP11") (pin "1") (pintype "passive"))
      (node (ref "U2") (pin "73") (pinfunction "PD11_73") (pintype "bidirectional"))
    )
    (net (code "56") (name "/DBG-PAD-3") (class "Default")
      (node (ref "TP7") (pin "1") (pintype "passive"))
      (node (ref "U2") (pin "35") (pinfunction "PA6_35") (pintype "bidirectional"))
    )
    (net (code "57") (name "/DBG-PAD-4") (class "Default")
      (node (ref "TP8") (pin "1") (pintype "passive"))
      (node (ref "U2") (pin "36") (pinfunction "PA7_36") (pintype "bidirectional"))
    )
    (net (code "58") (name "/DUT-A1") (class "Default")
      (node (ref "J1") (pin "19") (pinfunction "19_19") (pintype "passive"))
    )
    (net (code "59") (name "/DUT-A2") (class "Default")
      (node (ref "J1") (pin "20") (pinfunction "20_20") (pintype "passive"))
    )
    (net (code "60") (name "/DUT-B1") (class "Default")
      (node (ref "J1") (pin "5") (pinfunction "5_5") (pintype "passive"))
    )
    (net (code "61") (name "/DUT-B2") (class "Default")
      (node (ref "J1") (pin "6") (pinfunction "6_6") (pintype "passive"))
    )
    (net (code "62") (name "/DUT-BB11") (class "Default")
      (node (ref "J1") (pin "13") (pinfunction "13_13") (pintype "passive"))
    )
    (net (code "63") (name "/DUT-BB21") (class "Default")
      (node (ref "J1") (pin "11") (pinfunction "11_11") (pintype "passive"))
    )
    (net (code "64") (name "/DUT-C1") (class "Default")
      (node (ref "J1") (pin "17") (pinfunction "17_17") (pintype "passive"))
    )
    (net (code "65") (name "/DUT-C2") (class "Default")
      (node (ref "J1") (pin "18") (pinfunction "18_18") (pintype "passive"))
    )
    (net (code "66") (name "/DUT-D1") (class "Default")
      (node (ref "J1") (pin "7") (pinfunction "7_7") (pintype "passive"))
    )
    (net (code "67") (name "/DUT-D2") (class "Default")
      (node (ref "J1") (pin "8") (pinfunction "8_8") (pintype "passive"))
    )
    (net (code "68") (name "/DUT-E1") (class "Default")
      (node (ref "J1") (pin "15") (pinfunction "15_15") (pintype "passive"))
    )
    (net (code "69") (name "/DUT-E2") (class "Default")
      (node (ref "J1") (pin "16") (pinfunction "16_16") (pintype "passive"))
    )
    (net (code "70") (name "/DUT-F1") (class "Default")
      (node (ref "J1") (pin "9") (pinfunction "9_9") (pintype "passive"))
    )
    (net (code "71") (name "/DUT-F2") (class "Default")
      (node (ref "J1") (pin "10") (pinfunction "10_10") (pintype "passive"))
    )
    (net (code "72") (name "/DUT-GND-DIG") (class "Default")
      (node (ref "FB13") (pin "1") (pintype "passive"))
      (node (ref "J1") (pin "1") (pinfunction "1_1") (pintype "passive"))
    )
    (net (code "73") (name "/LEDDRV-DAC-CTRL-1") (class "Default")
      (node (ref "FB9") (pin "2") (pintype "passive"))
      (node (ref "U2") (pin "33") (pinfunction "PA4_33") (pintype "bidirectional"))
    )
    (net (code "74") (name "/LEDDRV-DAC-CTRL-2") (class "Default")
      (node (ref "FB10") (pin "1") (pintype "passive"))
      (node (ref "U2") (pin "34") (pinfunction "PA5_34") (pintype "bidirectional"))
    )
    (net (code "75") (name "/LEDDRV-GPIO-1") (class "Default")
      (node (ref "FB5") (pin "1") (pintype "passive"))
      (node (ref "U2") (pin "88") (pinfunction "PC9_88") (pintype "bidirectional"))
    )
    (net (code "76") (name "/LEDDRV-GPIO-2") (class "Default")
      (node (ref "FB6") (pin "2") (pintype "passive"))
      (node (ref "U2") (pin "87") (pinfunction "PC8_87") (pintype "bidirectional"))
    )
    (net (code "77") (name "/MCU-BOOT1") (class "Default")
      (node (ref "R5") (pin "2") (pinfunction "2_2") (pintype "passive"))
      (node (ref "TP2") (pin "1") (pintype "passive"))
      (node (ref "U2") (pin "123") (pinfunction "PB8-BOOT0_123") (pintype "bidirectional"))
    )
    (net (code "78") (name "/MCU-COMMS-RX") (class "Default")
      (node (ref "U2") (pin "101") (pinfunction "PC11_101") (pintype "bidirectional"))
    )
    (net (code "79") (name "/MCU-COMMS-TX") (class "Default")
      (node (ref "U2") (pin "100") (pinfunction "PC10_100") (pintype "bidirectional"))
    )
    (net (code "80") (name "/MCU-NRST") (class "Default")
      (node (ref "C21") (pin "1") (pinfunction "1_1") (pintype "passive"))
      (node (ref "CN1") (pin "12") (pinfunction "12_12") (pintype "passive"))
      (node (ref "P1") (pin "5") (pinfunction "5_5") (pintype "passive"))
      (node (ref "P3") (pin "1") (pinfunction "1_1") (pintype "passive"))
      (node (ref "U2") (pin "21") (pinfunction "PG10-NRST_21") (pintype "bidirectional"))
    )
    (net (code "81") (name "/MCU-SWCLK") (class "Default")
      (node (ref "CN1") (pin "6") (pinfunction "6_6") (pintype "passive"))
      (node (ref "P1") (pin "2") (pinfunction "2_2") (pintype "passive"))
      (node (ref "U2") (pin "98") (pinfunction "PA14_98") (pintype "bidirectional"))
    )
    (net (code "82") (name "/MCU-SWDIO") (class "Default")
      (node (ref "CN1") (pin "4") (pinfunction "4_4") (pintype "passive"))
      (node (ref "P1") (pin "4") (pinfunction "4_4") (pintype "passive"))
      (node (ref "U2") (pin "96") (pinfunction "PA13_96") (pintype "bidirectional"))
    )
    (net (code "83") (name "/MCU-SWO") (class "Default")
      (node (ref "CN1") (pin "8") (pinfunction "8_8") (pintype "passive"))
      (node (ref "P1") (pin "6") (pinfunction "6_6") (pintype "passive"))
      (node (ref "U2") (pin "118") (pinfunction "PB3_118") (pintype "bidirectional"))
    )
    (net (code "84") (name "/MCU-VREF") (class "Default")
      (node (ref "C14") (pin "2") (pinfunction "2_2") (pintype "passive"))
      (node (ref "R7") (pin "1") (pinfunction "1_1") (pintype "passive"))
      (node (ref "TP4") (pin "1") (pintype "passive"))
      (node (ref "U2") (pin "43") (pinfunction "VREF+_43") (pintype "power_in"))
      (node (ref "U2") (pin "44") (pinfunction "VREF+_44") (pintype "power_in"))
      (node (ref "U3") (pin "6") (pinfunction "VREF_6") (pintype "passive"))
    )
    (net (code "85") (name "/MCU_DBG_RX") (class "Default")
      (node (ref "CN1") (pin "14") (pinfunction "14_14") (pintype "passive"))
      (node (ref "P1") (pin "7") (pinfunction "7_7") (pintype "passive"))
      (node (ref "U2") (pin "106") (pinfunction "PG8_106") (pintype "bidirectional"))
    )
    (net (code "86") (name "/MCU_DBG_TX") (class "Default")
      (node (ref "CN1") (pin "13") (pinfunction "13_13") (pintype "passive"))
      (node (ref "P1") (pin "8") (pinfunction "8_8") (pintype "passive"))
      (node (ref "U2") (pin "105") (pinfunction "PG7_105") (pintype "bidirectional"))
    )
    (net (code "87") (name "/MCU_TDI") (class "Default")
      (node (ref "CN1") (pin "10") (pinfunction "10_10") (pintype "passive"))
      (node (ref "U2") (pin "99") (pinfunction "PA15_99") (pintype "bidirectional"))
    )
    (net (code "88") (name "/PWM-SETP-1") (class "Default")
      (node (ref "U2") (pin "76") (pinfunction "PD14_76") (pintype "bidirectional"))
    )
    (net (code "89") (name "/PWM-SETP-2") (class "Default")
      (node (ref "U2") (pin "91") (pinfunction "PA10_91") (pintype "bidirectional"))
    )
    (net (code "90") (name "/PWM-SETP-3") (class "Default")
      (node (ref "U2") (pin "77") (pinfunction "PD15_77") (pintype "bidirectional"))
    )
    (net (code "91") (name "/PWM-SETP-4") (class "Default")
      (node (ref "U2") (pin "92") (pinfunction "PA11_92") (pintype "bidirectional"))
    )
    (net (code "92") (name "/PWM-SETP-5") (class "Default")
      (node (ref "U2") (pin "90") (pinfunction "PA9_90") (pintype "bidirectional"))
    )
    (net (code "93") (name "/PWM-SETP-6") (class "Default")
      (node (ref "U2") (pin "93") (pinfunction "PA12_93") (pintype "bidirectional"))
    )
    (net (code "94") (name "/TEC-RX") (class "Default")
      (node (ref "FB2") (pin "2") (pintype "passive"))
      (node (ref "U2") (pin "125") (pinfunction "PE0_125") (pintype "bidirectional"))
    )
    (net (code "95") (name "/TEC-TX") (class "Default")
      (node (ref "FB12") (pin "2") (pintype "passive"))
      (node (ref "U2") (pin "126") (pinfunction "PE1_126") (pintype "bidirectional"))
    )
    (net (code "96") (name "/TEMP-SNS-ONEWIRE") (class "Default")
      (node (ref "FB7") (pin "1") (pintype "passive"))
      (node (ref "J1") (pin "2") (pinfunction "2_2") (pintype "passive"))
      (node (ref "U2") (pin "104") (pinfunction "PG6_104") (pintype "bidirectional"))
    )
    (net (code "97") (name "GND") (class "Default")
      (node (ref "C10") (pin "2") (pinfunction "2_2") (pintype "passive"))
      (node (ref "C11") (pin "1") (pinfunction "1_1") (pintype "passive"))
      (node (ref "C12") (pin "1") (pinfunction "1_1") (pintype "passive"))
      (node (ref "C13") (pin "2") (pinfunction "2_2") (pintype "passive"))
      (node (ref "C14") (pin "1") (pinfunction "1_1") (pintype "passive"))
      (node (ref "C15") (pin "2") (pinfunction "2_2") (pintype "passive"))
      (node (ref "C16") (pin "1") (pinfunction "1_1") (pintype "passive"))
      (node (ref "C17") (pin "1") (pinfunction "1_1") (pintype "passive"))
      (node (ref "C18") (pin "2") (pinfunction "2_2") (pintype "passive"))
      (node (ref "C19") (pin "2") (pinfunction "2_2") (pintype "passive"))
      (node (ref "C20") (pin "2") (pinfunction "2_2") (pintype "passive"))
      (node (ref "C21") (pin "2") (pinfunction "2_2") (pintype "passive"))
      (node (ref "C22") (pin "2") (pinfunction "2_2") (pintype "passive"))
      (node (ref "C23") (pin "2") (pinfunction "2_2") (pintype "passive"))
      (node (ref "C3") (pin "2") (pinfunction "2_2") (pintype "passive"))
      (node (ref "C4") (pin "2") (pinfunction "2_2") (pintype "passive"))
      (node (ref "C44") (pin "2") (pinfunction "2_2") (pintype "passive"))
      (node (ref "C45") (pin "2") (pinfunction "2_2") (pintype "passive"))
      (node (ref "C46") (pin "2") (pinfunction "2_2") (pintype "passive"))
      (node (ref "C47") (pin "2") (pinfunction "2_2") (pintype "passive"))
      (node (ref "C48") (pin "2") (pinfunction "2_2") (pintype "passive"))
      (node (ref "C49") (pin "2") (pinfunction "2_2") (pintype "passive"))
      (node (ref "C5") (pin "2") (pinfunction "2_2") (pintype "passive"))
      (node (ref "C6") (pin "2") (pinfunction "2_2") (pintype "passive"))
      (node (ref "C7") (pin "2") (pinfunction "2_2") (pintype "passive"))
      (node (ref "C74") (pin "2") (pinfunction "2_2") (pintype "passive"))
      (node (ref "C75") (pin "2") (pinfunction "2_2") (pintype "passive"))
      (node (ref "C76") (pin "2") (pinfunction "2_2") (pintype "passive"))
      (node (ref "C8") (pin "2") (pinfunction "2_2") (pintype "passive"))
      (node (ref "C9") (pin "2") (pinfunction "2_2") (pintype "passive"))
      (node (ref "CN1") (pin "5") (pinfunction "5_5") (pintype "passive"))
      (node (ref "CN1") (pin "7") (pinfunction "7_7") (pintype "passive"))
      (node (ref "D1") (pin "1") (pinfunction "C_1") (pintype "passive"))
      (node (ref "D2") (pin "1") (pinfunction "C_1") (pintype "passive"))
      (node (ref "FB13") (pin "2") (pintype "passive"))
      (node (ref "J2") (pin "6") (pinfunction "6_6") (pintype "passive"))
      (node (ref "J2") (pin "7") (pinfunction "7_7") (pintype "passive"))
      (node (ref "M1") (pin "2") (pinfunction "GND_2") (pintype "passive"))
      (node (ref "P1") (pin "3") (pinfunction "3_3") (pintype "passive"))
      (node (ref "P3") (pin "2") (pinfunction "2_2") (pintype "passive"))
      (node (ref "P4") (pin "2") (pinfunction "2_2") (pintype "passive"))
      (node (ref "P7") (pin "2") (pinfunction "2_2") (pintype "passive"))
      (node (ref "R5") (pin "1") (pinfunction "1_1") (pintype "passive"))
      (node (ref "R8") (pin "2") (pinfunction "2_2") (pintype "passive"))
      (node (ref "U2") (pin "110") (pinfunction "VSS_110") (pintype "power_in"))
      (node (ref "U2") (pin "12") (pinfunction "VSS_12") (pintype "power_in"))
      (node (ref "U2") (pin "127") (pinfunction "VSS_127") (pintype "power_in"))
      (node (ref "U2") (pin "30") (pinfunction "VSS_30") (pintype "power_in"))
      (node (ref "U2") (pin "42") (pinfunction "VSSA_42") (pintype "power_in"))
      (node (ref "U2") (pin "46") (pinfunction "VSS_46") (pintype "power_in"))
      (node (ref "U2") (pin "63") (pinfunction "VSS_63") (pintype "power_in"))
      (node (ref "U2") (pin "78") (pinfunction "VSS_78") (pintype "power_in"))
      (node (ref "U2") (pin "94") (pinfunction "VSS_94") (pintype "power_in"))
      (node (ref "U3") (pin "1") (pinfunction "GND_1") (pintype "power_in"))
      (node (ref "U3") (pin "2") (pinfunction "GND_2") (pintype "power_in"))
      (node (ref "Y1") (pin "2") (pinfunction "GND_2") (pintype "power_in"))
      (node (ref "Y1") (pin "4") (pinfunction "GND_4") (pintype "power_in"))
    )
    (net (code "98") (name "Net-(D1-A)") (class "Default")
      (node (ref "D1") (pin "2") (pinfunction "A_2") (pintype "passive"))
      (node (ref "R4") (pin "2") (pinfunction "2_2") (pintype "passive"))
    )
    (net (code "99") (name "Net-(D2-A)") (class "Default")
      (node (ref "D2") (pin "2") (pinfunction "A_2") (pintype "passive"))
      (node (ref "R6") (pin "2") (pinfunction "2_2") (pintype "passive"))
    )
    (net (code "100") (name "Net-(FB5-Pad2)") (class "Default")
      (node (ref "FB5") (pin "2") (pintype "passive"))
      (node (ref "J2") (pin "10") (pinfunction "10_10") (pintype "passive"))
    )
    (net (code "101") (name "Net-(FB6-Pad1)") (class "Default")
      (node (ref "FB6") (pin "1") (pintype "passive"))
      (node (ref "J2") (pin "11") (pinfunction "11_11") (pintype "passive"))
    )
    (net (code "102") (name "Net-(FB7-Pad2)") (class "Default")
      (node (ref "FB7") (pin "2") (pintype "passive"))
      (node (ref "J2") (pin "12") (pinfunction "12_12") (pintype "passive"))
    )
    (net (code "103") (name "Net-(FB8-Pad2)") (class "Default")
      (node (ref "FB8") (pin "2") (pintype "passive"))
      (node (ref "J2") (pin "14") (pinfunction "14_14") (pintype "passive"))
    )
    (net (code "104") (name "Net-(FB9-Pad1)") (class "Default")
      (node (ref "FB9") (pin "1") (pintype "passive"))
      (node (ref "J2") (pin "15") (pinfunction "15_15") (pintype "passive"))
    )
    (net (code "105") (name "Net-(FB10-Pad2)") (class "Default")
      (node (ref "FB10") (pin "2") (pintype "passive"))
      (node (ref "J2") (pin "16") (pinfunction "16_16") (pintype "passive"))
    )
    (net (code "106") (name "Net-(M1-RX)") (class "Default")
      (node (ref "FB2") (pin "1") (pintype "passive"))
      (node (ref "M1") (pin "7") (pinfunction "RX_7") (pintype "passive"))
    )
    (net (code "107") (name "Net-(M1-TX)") (class "Default")
      (node (ref "FB12") (pin "1") (pintype "passive"))
      (node (ref "M1") (pin "8") (pinfunction "TX_8") (pintype "passive"))
    )
    (net (code "108") (name "Net-(P7-Pad1)") (class "Default")
      (node (ref "P7") (pin "1") (pinfunction "1_1") (pintype "passive"))
      (node (ref "R7") (pin "2") (pinfunction "2_2") (pintype "passive"))
      (node (ref "R8") (pin "1") (pinfunction "1_1") (pintype "passive"))
    )
    (net (code "109") (name "Net-(U2A-PF1-OSC_OUT)") (class "Default")
      (node (ref "C22") (pin "1") (pinfunction "1_1") (pintype "passive"))
      (node (ref "U2") (pin "20") (pinfunction "PF1-OSC_OUT_20") (pintype "bidirectional"))
      (node (ref "Y1") (pin "3") (pinfunction "3_3") (pintype "passive"))
    )
    (net (code "110") (name "Net-(U2B-PF0-OSC_IN)") (class "Default")
      (node (ref "C20") (pin "1") (pinfunction "1_1") (pintype "passive"))
      (node (ref "U2") (pin "19") (pinfunction "PF0-OSC_IN_19") (pintype "bidirectional"))
      (node (ref "Y1") (pin "1") (pinfunction "1_1") (pintype "passive"))
    )
    (net (code "111") (name "Net-(U3-NR)") (class "Default")
      (node (ref "C15") (pin "1") (pinfunction "1_1") (pintype "passive"))
      (node (ref "U3") (pin "5") (pinfunction "NR_5") (pintype "passive"))
    )
    (net (code "112") (name "PWRGND") (class "Default")
      (node (ref "J2") (pin "3") (pinfunction "3_3") (pintype "passive"))
      (node (ref "J2") (pin "4") (pinfunction "4_4") (pintype "passive"))
    )
    (net (code "113") (name "unconnected-(CN1-Pad1)") (class "Default")
      (node (ref "CN1") (pin "1") (pinfunction "1_1") (pintype "passive+no_connect"))
    )
    (net (code "114") (name "unconnected-(CN1-Pad2)") (class "Default")
      (node (ref "CN1") (pin "2") (pinfunction "2_2") (pintype "passive+no_connect"))
    )
    (net (code "115") (name "unconnected-(CN1-Pad9)") (class "Default")
      (node (ref "CN1") (pin "9") (pinfunction "9_9") (pintype "passive+no_connect"))
    )
    (net (code "116") (name "unconnected-(CN1-Pad11)") (class "Default")
      (node (ref "CN1") (pin "11") (pinfunction "11_11") (pintype "passive+no_connect"))
    )
    (net (code "117") (name "unconnected-(J1-Pad4)") (class "Default")
      (node (ref "J1") (pin "4") (pinfunction "4_4") (pintype "passive+no_connect"))
    )
    (net (code "118") (name "unconnected-(J2-Pad8)") (class "Default")
      (node (ref "J2") (pin "8") (pinfunction "8_8") (pintype "passive+no_connect"))
    )
    (net (code "119") (name "unconnected-(J2-Pad9)") (class "Default")
      (node (ref "J2") (pin "9") (pinfunction "9_9") (pintype "passive+no_connect"))
    )
    (net (code "120") (name "unconnected-(J2-Pad13)") (class "Default")
      (node (ref "J2") (pin "13") (pinfunction "13_13") (pintype "passive+no_connect"))
    )
    (net (code "121") (name "unconnected-(M1-CANH-Pad9)") (class "Default")
      (node (ref "M1") (pin "9") (pinfunction "CANH_9") (pintype "passive+no_connect"))
    )
    (net (code "122") (name "unconnected-(M1-CANL-Pad10)") (class "Default")
      (node (ref "M1") (pin "10") (pinfunction "CANL_10") (pintype "passive+no_connect"))
    )
    (net (code "123") (name "unconnected-(M1-GPIO1-Pad3)") (class "Default")
      (node (ref "M1") (pin "3") (pinfunction "GPIO1_3") (pintype "passive+no_connect"))
    )
    (net (code "124") (name "unconnected-(M1-GPIO2-Pad4)") (class "Default")
      (node (ref "M1") (pin "4") (pinfunction "GPIO2_4") (pintype "passive+no_connect"))
    )
    (net (code "125") (name "unconnected-(M1-GPIO3-Pad5)") (class "Default")
      (node (ref "M1") (pin "5") (pinfunction "GPIO3_5") (pintype "passive+no_connect"))
    )
    (net (code "126") (name "unconnected-(M1-GPIO4-Pad6)") (class "Default")
      (node (ref "M1") (pin "6") (pinfunction "GPIO4_6") (pintype "passive+no_connect"))
    )
    (net (code "127") (name "unconnected-(U2A-PA2-Pad29)") (class "Default")
      (node (ref "U2") (pin "29") (pinfunction "PA2_29") (pintype "bidirectional+no_connect"))
    )
    (net (code "128") (name "unconnected-(U2A-PA3-Pad32)") (class "Default")
      (node (ref "U2") (pin "32") (pinfunction "PA3_32") (pintype "bidirectional"))
    )
    (net (code "129") (name "unconnected-(U2A-PA8-Pad89)") (class "Default")
      (node (ref "U2") (pin "89") (pinfunction "PA8_89") (pintype "bidirectional+no_connect"))
    )
    (net (code "130") (name "unconnected-(U2A-PB0-Pad39)") (class "Default")
      (node (ref "U2") (pin "39") (pinfunction "PB0_39") (pintype "bidirectional+no_connect"))
    )
    (net (code "131") (name "unconnected-(U2A-PB1-Pad40)") (class "Default")
      (node (ref "U2") (pin "40") (pinfunction "PB1_40") (pintype "bidirectional+no_connect"))
    )
    (net (code "132") (name "unconnected-(U2A-PB2-Pad41)") (class "Default")
      (node (ref "U2") (pin "41") (pinfunction "PB2_41") (pintype "bidirectional+no_connect"))
    )
    (net (code "133") (name "unconnected-(U2A-PB9-Pad124)") (class "Default")
      (node (ref "U2") (pin "124") (pinfunction "PB9_124") (pintype "bidirectional+no_connect"))
    )
    (net (code "134") (name "unconnected-(U2A-PB10-Pad62)") (class "Default")
      (node (ref "U2") (pin "62") (pinfunction "PB10_62") (pintype "bidirectional+no_connect"))
    )
    (net (code "135") (name "unconnected-(U2A-PB13-Pad67)") (class "Default")
      (node (ref "U2") (pin "67") (pinfunction "PB13_67") (pintype "bidirectional+no_connect"))
    )
    (net (code "136") (name "unconnected-(U2A-PB14-Pad68)") (class "Default")
      (node (ref "U2") (pin "68") (pinfunction "PB14_68") (pintype "bidirectional+no_connect"))
    )
    (net (code "137") (name "unconnected-(U2A-PB15-Pad69)") (class "Default")
      (node (ref "U2") (pin "69") (pinfunction "PB15_69") (pintype "bidirectional+no_connect"))
    )
    (net (code "138") (name "unconnected-(U2A-PC4-Pad37)") (class "Default")
      (node (ref "U2") (pin "37") (pinfunction "PC4_37") (pintype "bidirectional+no_connect"))
    )
    (net (code "139") (name "unconnected-(U2A-PC5-Pad38)") (class "Default")
      (node (ref "U2") (pin "38") (pinfunction "PC5_38") (pintype "bidirectional+no_connect"))
    )
    (net (code "140") (name "unconnected-(U2A-PC6-Pad80)") (class "Default")
      (node (ref "U2") (pin "80") (pinfunction "PC6_80") (pintype "bidirectional+no_connect"))
    )
    (net (code "141") (name "unconnected-(U2A-PC7-Pad81)") (class "Default")
      (node (ref "U2") (pin "81") (pinfunction "PC7_81") (pintype "bidirectional+no_connect"))
    )
    (net (code "142") (name "unconnected-(U2A-PC12-Pad102)") (class "Default")
      (node (ref "U2") (pin "102") (pinfunction "PC12_102") (pintype "bidirectional+no_connect"))
    )
    (net (code "143") (name "unconnected-(U2A-PD0-Pad108)") (class "Default")
      (node (ref "U2") (pin "108") (pinfunction "PD0_108") (pintype "bidirectional+no_connect"))
    )
    (net (code "144") (name "unconnected-(U2A-PD1-Pad109)") (class "Default")
      (node (ref "U2") (pin "109") (pinfunction "PD1_109") (pintype "bidirectional+no_connect"))
    )
    (net (code "145") (name "unconnected-(U2A-PD8-Pad70)") (class "Default")
      (node (ref "U2") (pin "70") (pinfunction "PD8_70") (pintype "bidirectional+no_connect"))
    )
    (net (code "146") (name "unconnected-(U2A-PD10-Pad72)") (class "Default")
      (node (ref "U2") (pin "72") (pinfunction "PD10_72") (pintype "bidirectional+no_connect"))
    )
    (net (code "147") (name "unconnected-(U2A-PD12-Pad74)") (class "Default")
      (node (ref "U2") (pin "74") (pinfunction "PD12_74") (pintype "bidirectional+no_connect"))
    )
    (net (code "148") (name "unconnected-(U2A-PD13-Pad75)") (class "Default")
      (node (ref "U2") (pin "75") (pinfunction "PD13_75") (pintype "bidirectional+no_connect"))
    )
    (net (code "149") (name "unconnected-(U2A-PE13-Pad59)") (class "Default")
      (node (ref "U2") (pin "59") (pinfunction "PE13_59") (pintype "bidirectional+no_connect"))
    )
    (net (code "150") (name "unconnected-(U2A-PE14-Pad60)") (class "Default")
      (node (ref "U2") (pin "60") (pinfunction "PE14_60") (pintype "bidirectional+no_connect"))
    )
    (net (code "151") (name "unconnected-(U2A-PE15-Pad61)") (class "Default")
      (node (ref "U2") (pin "61") (pinfunction "PE15_61") (pintype "bidirectional+no_connect"))
    )
    (net (code "152") (name "unconnected-(U2B-PF2-Pad26)") (class "Default")
      (node (ref "U2") (pin "26") (pinfunction "PF2_26") (pintype "bidirectional"))
    )
    (net (code "153") (name "unconnected-(U2B-PF5-Pad14)") (class "Default")
      (node (ref "U2") (pin "14") (pinfunction "PF5_14") (pintype "bidirectional+no_connect"))
    )
    (net (code "154") (name "unconnected-(U2B-PF6-Pad97)") (class "Default")
      (node (ref "U2") (pin "97") (pinfunction "PF6_97") (pintype "bidirectional+no_connect"))
    )
    (net (code "155") (name "unconnected-(U2B-PF11-Pad48)") (class "Default")
      (node (ref "U2") (pin "48") (pinfunction "PF11_48") (pintype "bidirectional+no_connect"))
    )
    (net (code "156") (name "unconnected-(U2B-PF12-Pad49)") (class "Default")
      (node (ref "U2") (pin "49") (pinfunction "PF12_49") (pintype "bidirectional+no_connect"))
    )
    (net (code "157") (name "unconnected-(U2B-PF13-Pad50)") (class "Default")
      (node (ref "U2") (pin "50") (pinfunction "PF13_50") (pintype "bidirectional+no_connect"))
    )
    (net (code "158") (name "unconnected-(U2B-PF14-Pad51)") (class "Default")
      (node (ref "U2") (pin "51") (pinfunction "PF14_51") (pintype "bidirectional+no_connect"))
    )
    (net (code "159") (name "unconnected-(U2B-PF15-Pad52)") (class "Default")
      (node (ref "U2") (pin "52") (pinfunction "PF15_52") (pintype "bidirectional+no_connect"))
    )
    (net (code "160") (name "unconnected-(U2B-PG0-Pad82)") (class "Default")
      (node (ref "U2") (pin "82") (pinfunction "PG0_82") (pintype "bidirectional+no_connect"))
    )
    (net (code "161") (name "unconnected-(U2B-PG1-Pad83)") (class "Default")
      (node (ref "U2") (pin "83") (pinfunction "PG1_83") (pintype "bidirectional+no_connect"))
    )
    (net (code "162") (name "unconnected-(U2B-PG2-Pad84)") (class "Default")
      (node (ref "U2") (pin "84") (pinfunction "PG2_84") (pintype "bidirectional+no_connect"))
    )
    (net (code "163") (name "unconnected-(U2B-PG3-Pad85)") (class "Default")
      (node (ref "U2") (pin "85") (pinfunction "PG3_85") (pintype "bidirectional+no_connect"))
    )
    (net (code "164") (name "unconnected-(U2B-PG4-Pad86)") (class "Default")
      (node (ref "U2") (pin "86") (pinfunction "PG4_86") (pintype "bidirectional+no_connect"))
    )
    (net (code "165") (name "unconnected-(U2B-PG5-Pad103)") (class "Default")
      (node (ref "U2") (pin "103") (pinfunction "PG5_103") (pintype "bidirectional+no_connect"))
    )
    (net (code "166") (name "unconnected-(U2B-PG9-Pad107)") (class "Default")
      (node (ref "U2") (pin "107") (pinfunction "PG9_107") (pintype "bidirectional+no_connect"))
    )
    (net (code "167") (name "unconnected-(U2C-VBAT-Pad6)") (class "Default")
      (node (ref "U2") (pin "6") (pinfunction "VBAT_6") (pintype "power_in+no_connect"))
    )
  )
)
